# Rotary_Encoder.net
KiCad netlist of a schematic drawn in EAGLE
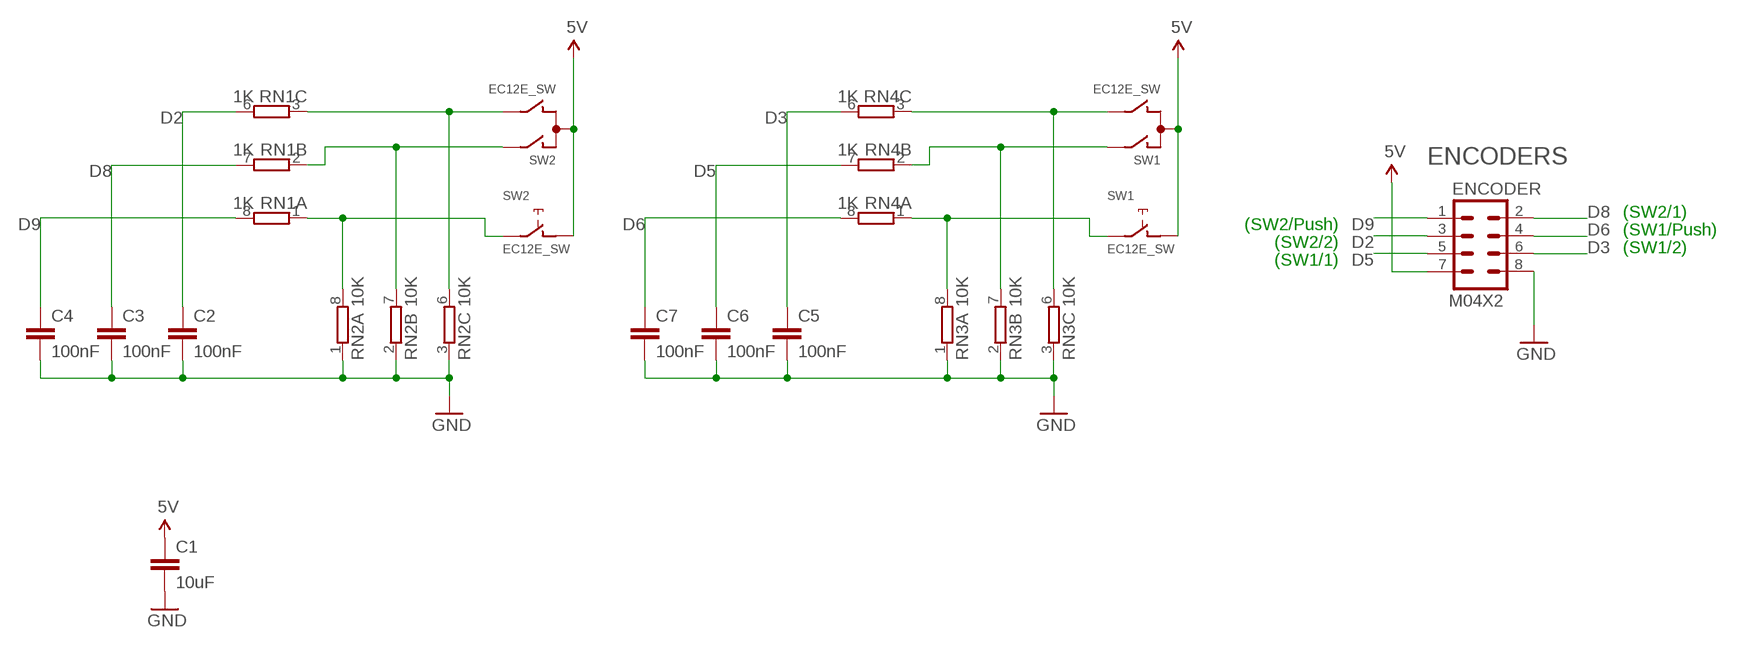
[diagram p0: schematic, sheet 1]

(export (version "E")
  (design (tool "Eeschema 10.0.6"))
  (components
    (comp (ref "C1")
      (value "10uF")
      (footprint "eagle-import:0603-CAP")
      (libsource (lib "eagle-import") (part "CAP0603-CAP"))
    )
    (comp (ref "C2")
      (value "100nF")
      (footprint "eagle-import:0603-CAP")
      (libsource (lib "eagle-import") (part "CAP0603-CAP"))
    )
    (comp (ref "C3")
      (value "100nF")
      (footprint "eagle-import:0603-CAP")
      (libsource (lib "eagle-import") (part "CAP0603-CAP"))
    )
    (comp (ref "C4")
      (value "100nF")
      (footprint "eagle-import:0603-CAP")
      (libsource (lib "eagle-import") (part "CAP0603-CAP"))
    )
    (comp (ref "C5")
      (value "100nF")
      (footprint "eagle-import:0603-CAP")
      (libsource (lib "eagle-import") (part "CAP0603-CAP"))
    )
    (comp (ref "C6")
      (value "100nF")
      (footprint "eagle-import:0603-CAP")
      (libsource (lib "eagle-import") (part "CAP0603-CAP"))
    )
    (comp (ref "C7")
      (value "100nF")
      (footprint "eagle-import:0603-CAP")
      (libsource (lib "eagle-import") (part "CAP0603-CAP"))
    )
    (comp (ref "ENCODER")
      (value "M04X2")
      (footprint "eagle-import:2X4")
      (libsource (lib "eagle-import") (part "M04X2"))
    )
    (comp (ref "RN1")
      (value "1K")
      (footprint "eagle-import:CAY16_HAND")
      (libsource (lib "eagle-import") (part "4R-NCAY16"))
    )
    (comp (ref "RN2")
      (value "10K")
      (footprint "eagle-import:CAY16_HAND")
      (libsource (lib "eagle-import") (part "4R-NCAY16"))
    )
    (comp (ref "RN3")
      (value "10K")
      (footprint "eagle-import:CAY16_HAND")
      (libsource (lib "eagle-import") (part "4R-NCAY16"))
    )
    (comp (ref "RN4")
      (value "1K")
      (footprint "eagle-import:CAY16_HAND")
      (libsource (lib "eagle-import") (part "4R-NCAY16"))
    )
    (comp (ref "SW1")
      (value "EC12E_SW")
      (footprint "eagle-import:ALPS_EC12E_SW")
      (fields (field (name "MPN") "EC12E2424407"))
      (libsource (lib "eagle-import") (part "EC12E_SW"))
    )
    (comp (ref "SW2")
      (value "EC12E_SW")
      (footprint "eagle-import:ALPS_EC12E_SW")
      (fields (field (name "MPN") "EC12E2424407"))
      (libsource (lib "eagle-import") (part "EC12E_SW"))
    )
  )
  (nets
    (net (code "1") (name "/D2") (class "Default")
      (node (ref "C2") (pin "1") (pinfunction "1_1") (pintype "passive"))
      (node (ref "ENCODER") (pin "3") (pinfunction "3_3") (pintype "passive"))
      (node (ref "RN1") (pin "6") (pinfunction "2_6") (pintype "passive"))
    )
    (net (code "2") (name "/D3") (class "Default")
      (node (ref "C5") (pin "1") (pinfunction "1_1") (pintype "passive"))
      (node (ref "ENCODER") (pin "6") (pinfunction "6_6") (pintype "passive"))
      (node (ref "RN4") (pin "6") (pinfunction "2_6") (pintype "passive"))
    )
    (net (code "3") (name "/D5") (class "Default")
      (node (ref "C6") (pin "1") (pinfunction "1_1") (pintype "passive"))
      (node (ref "ENCODER") (pin "5") (pinfunction "5_5") (pintype "passive"))
      (node (ref "RN4") (pin "7") (pinfunction "2_7") (pintype "passive"))
    )
    (net (code "4") (name "/D6") (class "Default")
      (node (ref "C7") (pin "1") (pinfunction "1_1") (pintype "passive"))
      (node (ref "ENCODER") (pin "4") (pinfunction "4_4") (pintype "passive"))
      (node (ref "RN4") (pin "8") (pinfunction "2_8") (pintype "passive"))
    )
    (net (code "5") (name "/D8") (class "Default")
      (node (ref "C3") (pin "1") (pinfunction "1_1") (pintype "passive"))
      (node (ref "ENCODER") (pin "2") (pinfunction "2_2") (pintype "passive"))
      (node (ref "RN1") (pin "7") (pinfunction "2_7") (pintype "passive"))
    )
    (net (code "6") (name "/D9") (class "Default")
      (node (ref "C4") (pin "1") (pinfunction "1_1") (pintype "passive"))
      (node (ref "ENCODER") (pin "1") (pinfunction "1_1") (pintype "passive"))
      (node (ref "RN1") (pin "8") (pinfunction "2_8") (pintype "passive"))
    )
    (net (code "7") (name "5V") (class "Default")
      (node (ref "C1") (pin "1") (pinfunction "1_1") (pintype "passive"))
      (node (ref "ENCODER") (pin "7") (pinfunction "7_7") (pintype "passive"))
      (node (ref "SW1") (pin "C") (pinfunction "C_C") (pintype "passive"))
      (node (ref "SW1") (pin "D") (pinfunction "1_D") (pintype "passive"))
      (node (ref "SW2") (pin "C") (pinfunction "C_C") (pintype "passive"))
      (node (ref "SW2") (pin "D") (pinfunction "1_D") (pintype "passive"))
    )
    (net (code "8") (name "GND") (class "Default")
      (node (ref "C1") (pin "2") (pinfunction "2_2") (pintype "passive"))
      (node (ref "C2") (pin "2") (pinfunction "2_2") (pintype "passive"))
      (node (ref "C3") (pin "2") (pinfunction "2_2") (pintype "passive"))
      (node (ref "C4") (pin "2") (pinfunction "2_2") (pintype "passive"))
      (node (ref "C5") (pin "2") (pinfunction "2_2") (pintype "passive"))
      (node (ref "C6") (pin "2") (pinfunction "2_2") (pintype "passive"))
      (node (ref "C7") (pin "2") (pinfunction "2_2") (pintype "passive"))
      (node (ref "ENCODER") (pin "8") (pinfunction "8_8") (pintype "passive"))
      (node (ref "RN2") (pin "1") (pinfunction "1_1") (pintype "passive"))
      (node (ref "RN2") (pin "2") (pinfunction "1_2") (pintype "passive"))
      (node (ref "RN2") (pin "3") (pinfunction "1_3") (pintype "passive"))
      (node (ref "RN3") (pin "1") (pinfunction "1_1") (pintype "passive"))
      (node (ref "RN3") (pin "2") (pinfunction "1_2") (pintype "passive"))
      (node (ref "RN3") (pin "3") (pinfunction "1_3") (pintype "passive"))
    )
    (net (code "9") (name "Net-(RN1B-1)") (class "Default")
      (node (ref "RN1") (pin "2") (pinfunction "1_2") (pintype "passive"))
      (node (ref "RN2") (pin "7") (pinfunction "2_7") (pintype "passive"))
      (node (ref "SW2") (pin "A") (pinfunction "A_A") (pintype "passive"))
    )
    (net (code "10") (name "Net-(RN1C-1)") (class "Default")
      (node (ref "RN1") (pin "3") (pinfunction "1_3") (pintype "passive"))
      (node (ref "RN2") (pin "6") (pinfunction "2_6") (pintype "passive"))
      (node (ref "SW2") (pin "B") (pinfunction "B_B") (pintype "passive"))
    )
    (net (code "11") (name "Net-(RN2A-2)") (class "Default")
      (node (ref "RN1") (pin "1") (pinfunction "1_1") (pintype "passive"))
      (node (ref "RN2") (pin "8") (pinfunction "2_8") (pintype "passive"))
      (node (ref "SW2") (pin "E") (pinfunction "2_E") (pintype "passive"))
    )
    (net (code "12") (name "Net-(RN3A-2)") (class "Default")
      (node (ref "RN3") (pin "8") (pinfunction "2_8") (pintype "passive"))
      (node (ref "RN4") (pin "1") (pinfunction "1_1") (pintype "passive"))
      (node (ref "SW1") (pin "E") (pinfunction "2_E") (pintype "passive"))
    )
    (net (code "13") (name "Net-(RN3B-2)") (class "Default")
      (node (ref "RN3") (pin "7") (pinfunction "2_7") (pintype "passive"))
      (node (ref "RN4") (pin "2") (pinfunction "1_2") (pintype "passive"))
      (node (ref "SW1") (pin "A") (pinfunction "A_A") (pintype "passive"))
    )
    (net (code "14") (name "Net-(RN3C-2)") (class "Default")
      (node (ref "RN3") (pin "6") (pinfunction "2_6") (pintype "passive"))
      (node (ref "RN4") (pin "3") (pinfunction "1_3") (pintype "passive"))
      (node (ref "SW1") (pin "B") (pinfunction "B_B") (pintype "passive"))
    )
  )
)
